# LB_-_Supply.net
KiCad netlist of a schematic drawn in Altium Designer
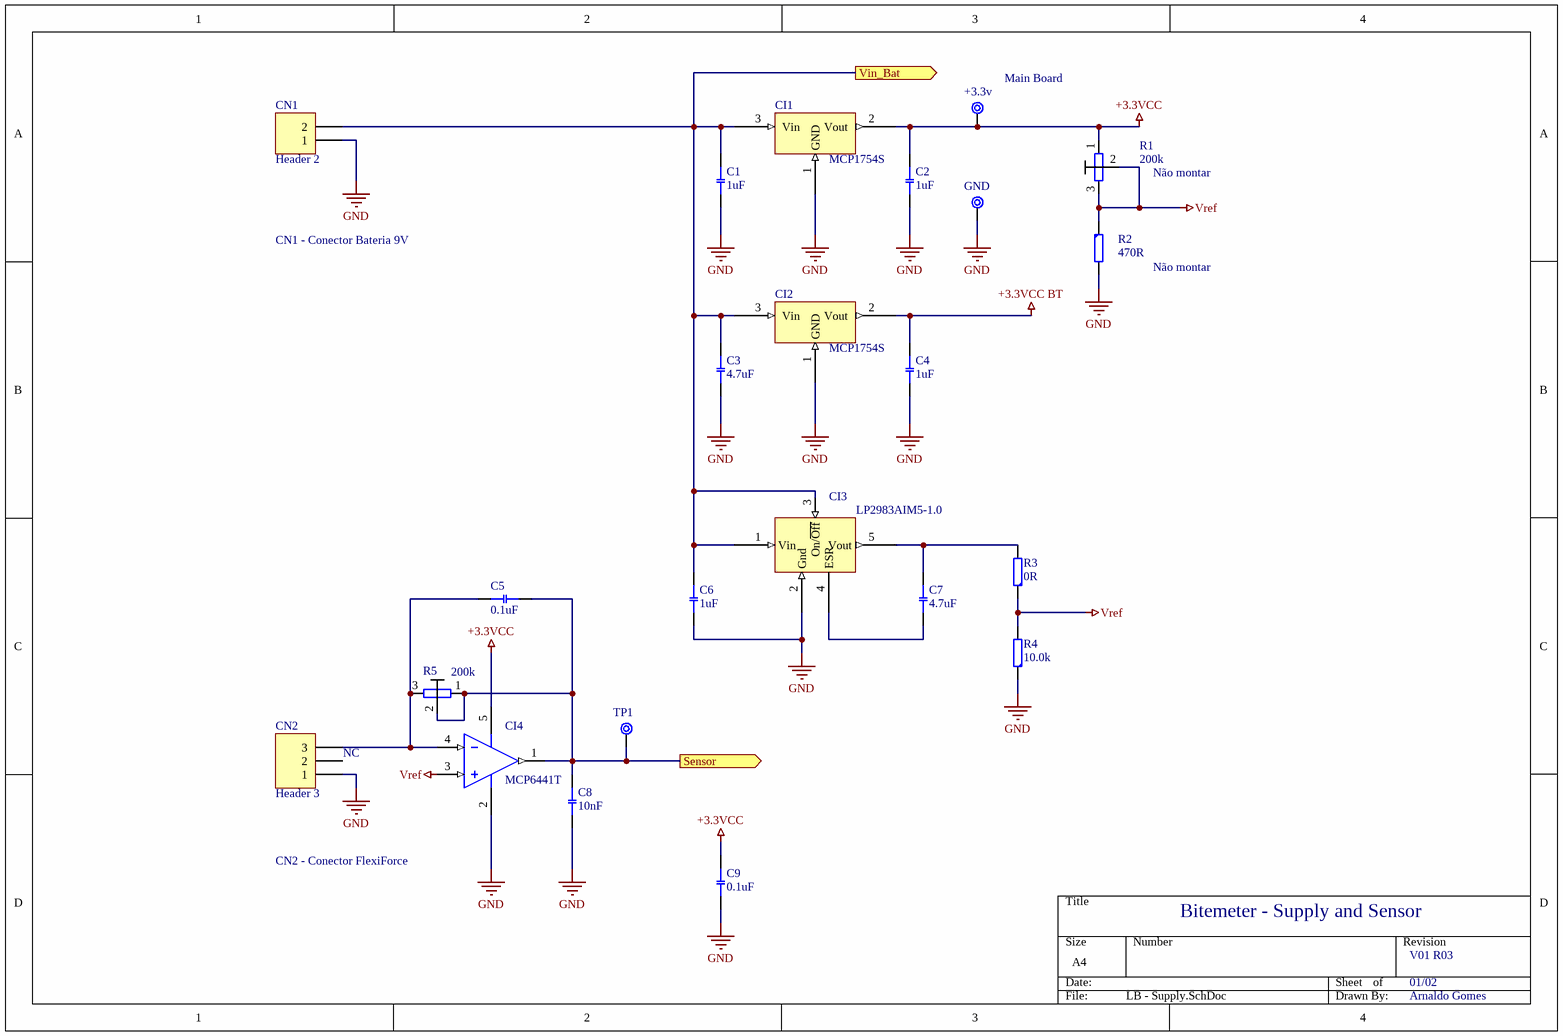
[diagram p0: LB - Supply.SchDoc]

(export (version "E")
  (design (tool "Eeschema 10.0.6"))
  (components
    (comp (ref "+3.3v")
      (value "TP")
      (footprint "TPSMD")
      (description "Test Point")
      (libsource (lib "LB - V01-R01") (part "TP"))
    )
    (comp (ref "C1")
      (value "1uF")
      (footprint "R0805")
      (description "Capictor Cerâmico 4.7uFx16V")
      (libsource (lib "") (part "C_1"))
    )
    (comp (ref "C2")
      (value "1uF")
      (footprint "R0805")
      (description "Capictor Cerâmico 1uFx16V")
      (libsource (lib "") (part "C_1"))
    )
    (comp (ref "C3")
      (value "4.7uF")
      (footprint "R0805")
      (description "Capictor Cerâmico 4.7uFx16V")
      (libsource (lib "") (part "C_1"))
    )
    (comp (ref "C4")
      (value "1uF")
      (footprint "R0805")
      (description "Capictor Cerâmico 1uFx16V")
      (libsource (lib "") (part "C_1"))
    )
    (comp (ref "C5")
      (value "0.1uF")
      (footprint "R0805")
      (description "Capacitor 0.1uFx25V")
      (libsource (lib "") (part "C_1"))
    )
    (comp (ref "C6")
      (value "1uF")
      (footprint "R0805")
      (description "Capictor Cerâmico 1uFx16V")
      (libsource (lib "LB - V01-R01") (part "C"))
    )
    (comp (ref "C7")
      (value "4.7uF")
      (footprint "R0805")
      (description "Capictor Cerâmico 4.7uFx16V")
      (libsource (lib "") (part "C_1"))
    )
    (comp (ref "C8")
      (value "10nF")
      (footprint "R0805")
      (description "Capacitor 10nFx25V")
      (libsource (lib "") (part "C_1"))
    )
    (comp (ref "C9")
      (value "0.1uF")
      (footprint "R0805")
      (description "Capacitor 0.1uFx25V")
      (libsource (lib "") (part "C_1"))
    )
    (comp (ref "CI1")
      (value "MCP1754S")
      (footprint "SOT23-A MCP1754")
      (description "Regulador 3.3V MCP1754S")
      (libsource (lib "LB - V01-R01") (part "Regulador 3.3V - SOT223-3, 4-Leads, Body 6.50x7.00mm (avg), Pitch 2.30mm, IPC Medium_1"))
    )
    (comp (ref "CI2")
      (value "MCP1754S")
      (footprint "SOT23-A MCP1754")
      (description "Regulador 3.3V MCP1754S")
      (libsource (lib "LB - V01-R01") (part "Regulador 3.3V - SOT223-3, 4-Leads, Body 6.50x7.00mm (avg), Pitch 2.30mm, IPC Medium_1"))
    )
    (comp (ref "CI3")
      (value "LP2983AIM5-1.0")
      (footprint "SOT23-5 Amp Op")
      (description "Regulador 1.0V")
      (libsource (lib "LB - V01-R01") (part "Regulador 1.0V - SOT23-5"))
    )
    (comp (ref "CI4")
      (value "MCP6441T")
      (footprint "SOT23-5 Amp Op")
      (description "Amp Op Rail-to-Rail")
      (libsource (lib "LB - V01-R01") (part "Amp Op"))
    )
    (comp (ref "CN1")
      (value "Header 2")
      (footprint "HDR1X2")
      (description "Header, 2-Pin")
      (libsource (lib "LB - V01-R01") (part "Conector Alimentação"))
    )
    (comp (ref "CN2")
      (value "Header 3")
      (footprint "HDR1X3")
      (description "Header, 3-Pin")
      (libsource (lib "LB - V01-R01") (part "Conector Sensor"))
    )
    (comp (ref "GND")
      (value "TP")
      (footprint "TPSMD")
      (description "Test Point")
      (libsource (lib "LB - V01-R01") (part "TP"))
    )
    (comp (ref "R1")
      (value "200k")
      (footprint "3364X-1-503E")
      (description "Trimpot 200k")
      (libsource (lib "LB - V01-R01") (part "Trimpot"))
    )
    (comp (ref "R2") (value "470R") (footprint "R0805") (libsource (lib "LB - V01-R01") (part "R")))
    (comp (ref "R3") (value "0R") (footprint "R0805") (libsource (lib "LB - V01-R01") (part "R")))
    (comp (ref "R4") (value "10.0k") (footprint "R0805") (libsource (lib "LB - V01-R01") (part "R")))
    (comp (ref "R5")
      (value "200k")
      (footprint "3364X-1-503E")
      (description "Trimpot 500k")
      (libsource (lib "LB - V01-R01") (part "Trimpot"))
    )
    (comp (ref "TP1")
      (value "TP")
      (footprint "TPSMD")
      (description "Test Point")
      (libsource (lib "LB - V01-R01") (part "TP"))
    )
  )
  (nets
    (net (code "1") (name "+3.3VCC") (class "Default")
      (node (ref "+3.3v") (pin "1") (pinfunction "1_1") (pintype "passive"))
      (node (ref "C2") (pin "2") (pinfunction "B_2") (pintype "passive"))
      (node (ref "C9") (pin "2") (pinfunction "B_2") (pintype "passive"))
      (node (ref "CI1") (pin "2") (pinfunction "Vout_2") (pintype "output"))
      (node (ref "CI4") (pin "5") (pinfunction "VDD_5") (pintype "passive"))
      (node (ref "R1") (pin "1") (pinfunction "B_1") (pintype "passive"))
    )
    (net (code "2") (name "+3.3VCC BT") (class "Default")
      (node (ref "C4") (pin "2") (pinfunction "B_2") (pintype "passive"))
      (node (ref "CI2") (pin "2") (pinfunction "Vout_2") (pintype "output"))
    )
    (net (code "3") (name "/Sensor") (class "Default")
      (node (ref "C5") (pin "1") (pinfunction "A_1") (pintype "passive"))
      (node (ref "C8") (pin "2") (pinfunction "B_2") (pintype "passive"))
      (node (ref "CI4") (pin "1") (pinfunction "Vout_1") (pintype "output"))
      (node (ref "R5") (pin "1") (pinfunction "B_1") (pintype "passive"))
      (node (ref "R5") (pin "2") (pinfunction "C_2") (pintype "passive"))
      (node (ref "TP1") (pin "1") (pinfunction "1_1") (pintype "passive"))
    )
    (net (code "4") (name "/Vin_Bat") (class "Default")
      (node (ref "C1") (pin "2") (pinfunction "B_2") (pintype "passive"))
      (node (ref "C3") (pin "2") (pinfunction "B_2") (pintype "passive"))
      (node (ref "C6") (pin "1") (pinfunction "A_1") (pintype "passive"))
      (node (ref "CI1") (pin "3") (pinfunction "Vin_3") (pintype "input"))
      (node (ref "CI2") (pin "3") (pinfunction "Vin_3") (pintype "input"))
      (node (ref "CI3") (pin "1") (pinfunction "Vin_1") (pintype "input"))
      (node (ref "CI3") (pin "3") (pinfunction "On/~{Off}_3") (pintype "input"))
      (node (ref "CN1") (pin "2") (pinfunction "2_2") (pintype "passive"))
    )
    (net (code "5") (name "GND") (class "Default")
      (node (ref "C1") (pin "1") (pinfunction "A_1") (pintype "passive"))
      (node (ref "C2") (pin "1") (pinfunction "A_1") (pintype "passive"))
      (node (ref "C3") (pin "1") (pinfunction "A_1") (pintype "passive"))
      (node (ref "C4") (pin "1") (pinfunction "A_1") (pintype "passive"))
      (node (ref "C6") (pin "2") (pinfunction "B_2") (pintype "passive"))
      (node (ref "C8") (pin "1") (pinfunction "A_1") (pintype "passive"))
      (node (ref "C9") (pin "1") (pinfunction "A_1") (pintype "passive"))
      (node (ref "CI1") (pin "1") (pinfunction "GND_1") (pintype "input"))
      (node (ref "CI2") (pin "1") (pinfunction "GND_1") (pintype "input"))
      (node (ref "CI3") (pin "2") (pinfunction "Gnd_2") (pintype "input"))
      (node (ref "CI4") (pin "2") (pinfunction "VSS_2") (pintype "passive"))
      (node (ref "CN1") (pin "1") (pinfunction "1_1") (pintype "passive"))
      (node (ref "CN2") (pin "1") (pinfunction "1_1") (pintype "passive"))
      (node (ref "GND") (pin "1") (pinfunction "1_1") (pintype "passive"))
      (node (ref "R2") (pin "2") (pinfunction "B_2") (pintype "passive"))
      (node (ref "R4") (pin "1") (pinfunction "A_1") (pintype "passive"))
    )
    (net (code "6") (name "Net-(C5-B)") (class "Default")
      (node (ref "C5") (pin "2") (pinfunction "B_2") (pintype "passive"))
      (node (ref "CI4") (pin "4") (pinfunction "Vin-_4") (pintype "input"))
      (node (ref "CN2") (pin "3") (pinfunction "3_3") (pintype "passive"))
      (node (ref "R5") (pin "3") (pinfunction "A_3") (pintype "passive"))
    )
    (net (code "7") (name "Net-(C7-A)") (class "Default")
      (node (ref "C7") (pin "1") (pinfunction "A_1") (pintype "passive"))
      (node (ref "CI3") (pin "4") (pinfunction "ESR_4") (pintype "passive"))
    )
    (net (code "8") (name "Net-(C7-B)") (class "Default")
      (node (ref "C7") (pin "2") (pinfunction "B_2") (pintype "passive"))
      (node (ref "CI3") (pin "5") (pinfunction "Vout_5") (pintype "output"))
      (node (ref "R3") (pin "2") (pinfunction "B_2") (pintype "passive"))
    )
    (net (code "9") (name "Vref") (class "Default")
      (node (ref "CI4") (pin "3") (pinfunction "Vin+_3") (pintype "input"))
      (node (ref "R1") (pin "2") (pinfunction "C_2") (pintype "passive"))
      (node (ref "R1") (pin "3") (pinfunction "A_3") (pintype "passive"))
      (node (ref "R2") (pin "1") (pinfunction "A_1") (pintype "passive"))
      (node (ref "R3") (pin "1") (pinfunction "A_1") (pintype "passive"))
      (node (ref "R4") (pin "2") (pinfunction "B_2") (pintype "passive"))
    )
    (net (code "10") (name "unconnected-(CN2-Pad2)") (class "Default")
      (node (ref "CN2") (pin "2") (pinfunction "2_2") (pintype "passive"))
    )
  )
)
